# BIXS-V1_5.net
KiCad netlist of a schematic drawn in EAGLE
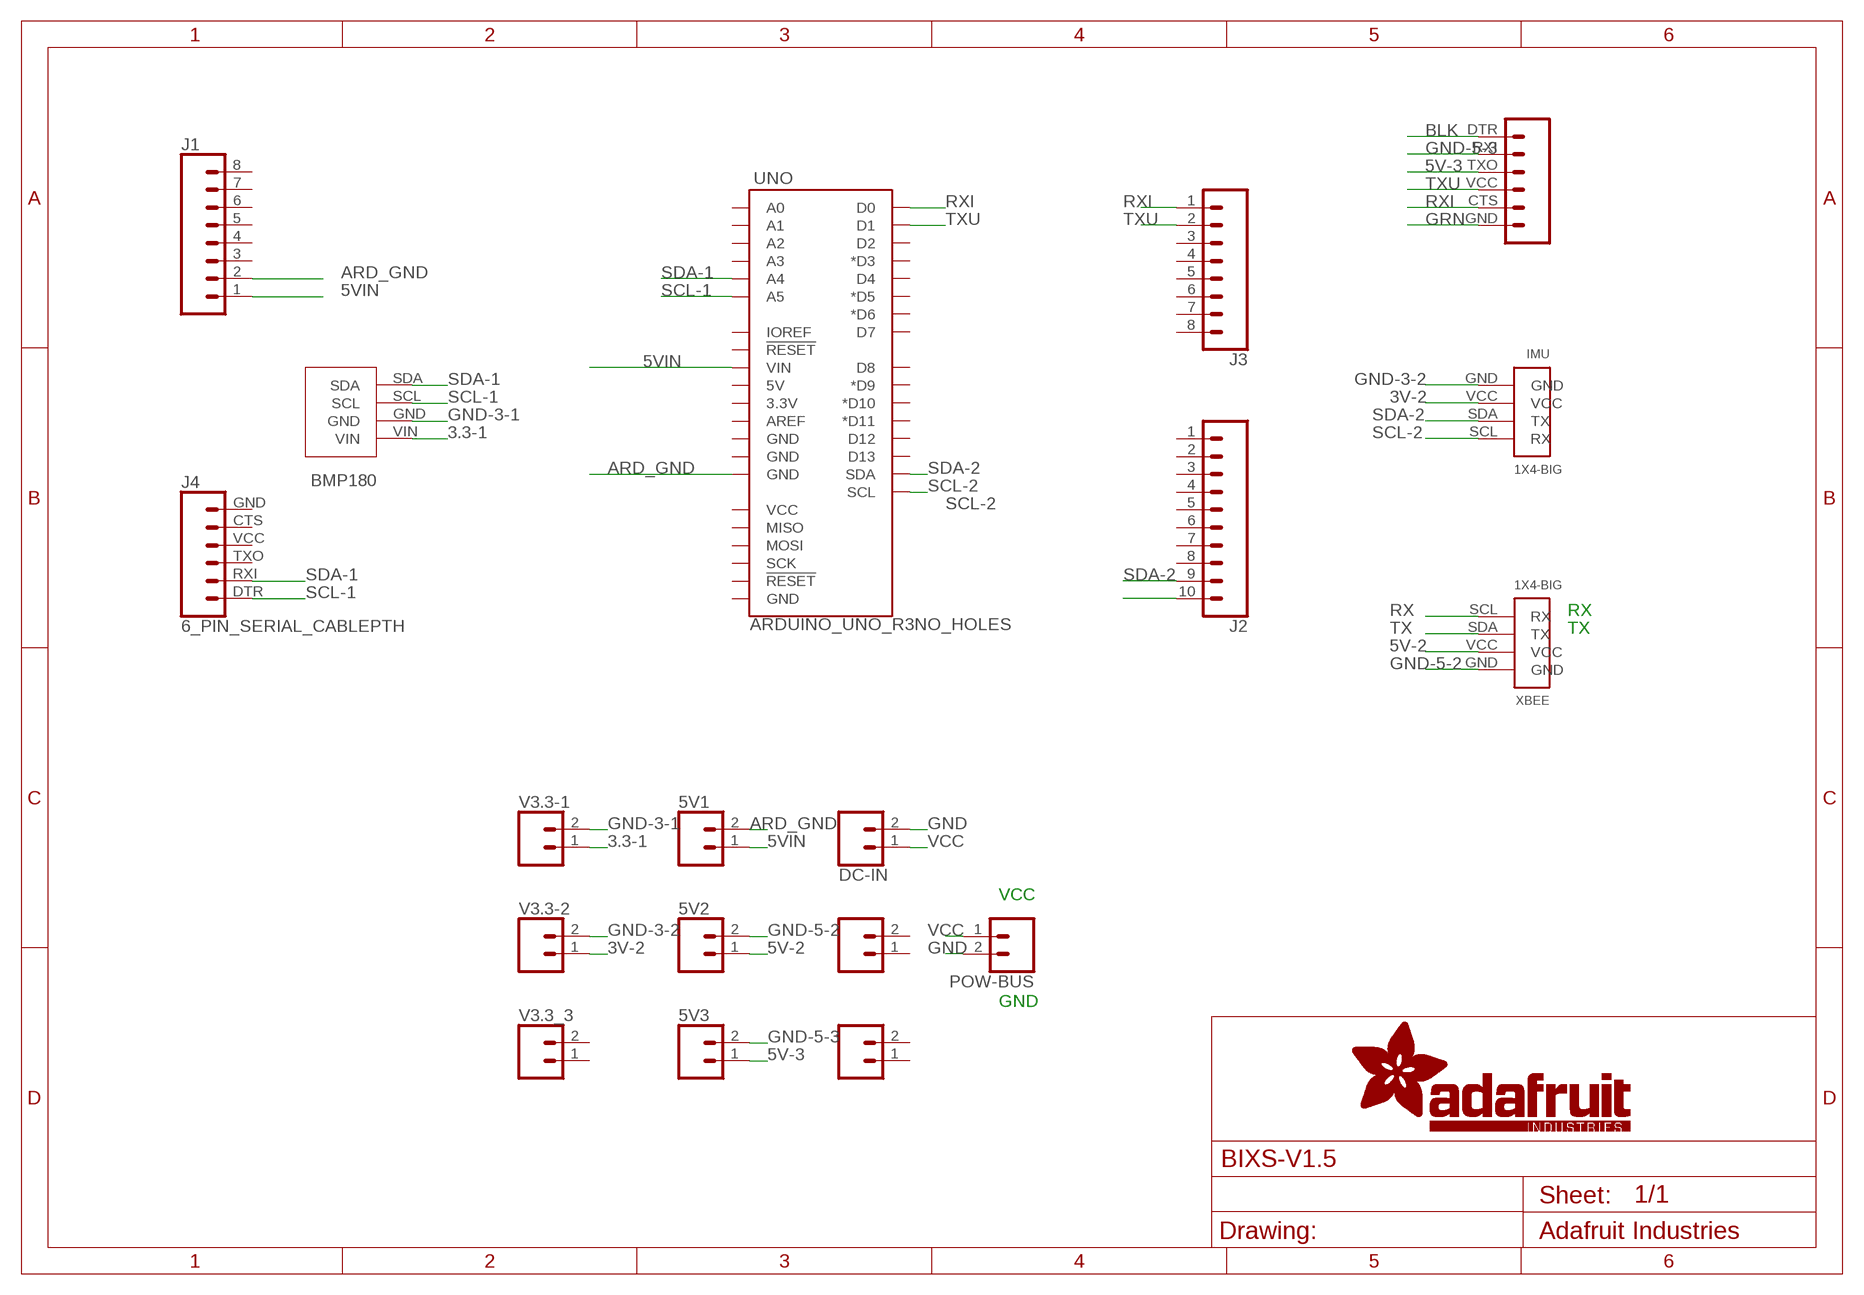
[diagram p0: schematic, sheet 1]

(export (version "E")
  (design (tool "Eeschema 10.0.6"))
  (components
    (comp (ref "5V1")
      (value "CONN_02")
      (footprint "eagle-import:1X02")
      (libsource (lib "eagle-import") (part "CONN_02"))
    )
    (comp (ref "5V2")
      (value "CONN_02")
      (footprint "eagle-import:1X02")
      (libsource (lib "eagle-import") (part "CONN_02"))
    )
    (comp (ref "5V3")
      (value "CONN_02")
      (footprint "eagle-import:1X02")
      (libsource (lib "eagle-import") (part "CONN_02"))
    )
    (comp (ref "BMP1")
      (value "BMP180")
      (footprint "eagle-import:BMP180")
      (libsource (lib "eagle-import") (part "BMP180"))
    )
    (comp (ref "DC_1")
      (value "CONN_02")
      (footprint "eagle-import:1X02")
      (libsource (lib "eagle-import") (part "CONN_02"))
    )
    (comp (ref "DC_2")
      (value "CONN_02")
      (footprint "eagle-import:1X02")
      (libsource (lib "eagle-import") (part "CONN_02"))
    )
    (comp (ref "DC_IN")
      (value "DC-IN")
      (footprint "eagle-import:1X02")
      (libsource (lib "eagle-import") (part "CONN_02"))
    )
    (comp (ref "IMU")
      (value "1X4-BIG")
      (footprint "eagle-import:1X04-BIG")
      (libsource (lib "eagle-import") (part "1X4-BIG"))
    )
    (comp (ref "J1")
      (value "CONN_08\"")
      (footprint "eagle-import:1X08")
      (libsource (lib "eagle-import") (part "CONN_08{dblquote}"))
    )
    (comp (ref "J2")
      (value "CONN_10\"")
      (footprint "eagle-import:1X10")
      (libsource (lib "eagle-import") (part "CONN_10{dblquote}"))
    )
    (comp (ref "J3")
      (value "CONN_08\"")
      (footprint "eagle-import:1X08")
      (libsource (lib "eagle-import") (part "CONN_08{dblquote}"))
    )
    (comp (ref "J4")
      (value "6_PIN_SERIAL_CABLEPTH")
      (footprint "eagle-import:FTDI_BASIC")
      (libsource (lib "eagle-import") (part "6_PIN_SERIAL_CABLEPTH"))
    )
    (comp (ref "MSD")
      (value "6_PIN_SERIAL_CABLEPTH")
      (footprint "eagle-import:FTDI_BASIC")
      (libsource (lib "eagle-import") (part "6_PIN_SERIAL_CABLEPTH"))
    )
    (comp (ref "POW-BUS")
      (value "CONN_02")
      (footprint "eagle-import:1X02")
      (libsource (lib "eagle-import") (part "CONN_02"))
    )
    (comp (ref "UNO")
      (value "ARDUINO_UNO_R3NO_HOLES")
      (footprint "eagle-import:ARDUINO_R3_NO_HOLES")
      (libsource (lib "eagle-import") (part "ARDUINO_UNO_R3NO_HOLES"))
    )
    (comp (ref "V3.3-1")
      (value "CONN_02")
      (footprint "eagle-import:1X02")
      (libsource (lib "eagle-import") (part "CONN_02"))
    )
    (comp (ref "V3.3-2")
      (value "CONN_02")
      (footprint "eagle-import:1X02")
      (libsource (lib "eagle-import") (part "CONN_02"))
    )
    (comp (ref "V3.3_3")
      (value "CONN_02")
      (footprint "eagle-import:1X02")
      (libsource (lib "eagle-import") (part "CONN_02"))
    )
    (comp (ref "XBEE")
      (value "1X4-BIG")
      (footprint "eagle-import:1X04-BIG")
      (libsource (lib "eagle-import") (part "1X4-BIG"))
    )
  )
  (nets
    (net (code "1") (name "/3.3-1") (class "Default")
      (node (ref "BMP1") (pin "VIN") (pinfunction "VIN_VIN") (pintype "bidirectional"))
      (node (ref "V3.3-1") (pin "1") (pinfunction "1_1") (pintype "passive"))
    )
    (net (code "2") (name "/3V-2") (class "Default")
      (node (ref "IMU") (pin "VCC") (pinfunction "VCC_VCC") (pintype "bidirectional"))
      (node (ref "V3.3-2") (pin "1") (pinfunction "1_1") (pintype "passive"))
    )
    (net (code "3") (name "/5V-2") (class "Default")
      (node (ref "5V2") (pin "1") (pinfunction "1_1") (pintype "passive"))
      (node (ref "XBEE") (pin "VCC") (pinfunction "VCC_VCC") (pintype "bidirectional"))
    )
    (net (code "4") (name "/5V-3") (class "Default")
      (node (ref "5V3") (pin "1") (pinfunction "1_1") (pintype "passive"))
      (node (ref "MSD") (pin "TXO") (pinfunction "VCC_TXO") (pintype "passive"))
    )
    (net (code "5") (name "/5VIN") (class "Default")
      (node (ref "5V1") (pin "1") (pinfunction "1_1") (pintype "passive"))
      (node (ref "J1") (pin "1") (pinfunction "1_1") (pintype "passive"))
      (node (ref "UNO") (pin "VIN") (pinfunction "VIN_VIN") (pintype "bidirectional"))
    )
    (net (code "6") (name "/ARD_GND") (class "Default")
      (node (ref "5V1") (pin "2") (pinfunction "2_2") (pintype "passive"))
      (node (ref "J1") (pin "2") (pinfunction "2_2") (pintype "passive"))
      (node (ref "UNO") (pin "GND@2") (pinfunction "GND_GND@2") (pintype "bidirectional"))
    )
    (net (code "7") (name "/BLK") (class "Default")
      (node (ref "MSD") (pin "DTR") (pinfunction "BLK_DTR") (pintype "passive"))
    )
    (net (code "8") (name "/GND") (class "Default")
      (node (ref "DC_IN") (pin "2") (pinfunction "2_2") (pintype "passive"))
      (node (ref "POW-BUS") (pin "2") (pinfunction "2_2") (pintype "passive"))
    )
    (net (code "9") (name "/GND-3-1") (class "Default")
      (node (ref "BMP1") (pin "GND") (pinfunction "GND_GND") (pintype "bidirectional"))
      (node (ref "V3.3-1") (pin "2") (pinfunction "2_2") (pintype "passive"))
    )
    (net (code "10") (name "/GND-3-2") (class "Default")
      (node (ref "IMU") (pin "GND") (pinfunction "GND_GND") (pintype "bidirectional"))
      (node (ref "V3.3-2") (pin "2") (pinfunction "2_2") (pintype "passive"))
    )
    (net (code "11") (name "/GND-5-2") (class "Default")
      (node (ref "5V2") (pin "2") (pinfunction "2_2") (pintype "passive"))
      (node (ref "XBEE") (pin "GND") (pinfunction "GND_GND") (pintype "bidirectional"))
    )
    (net (code "12") (name "/GND-5-3") (class "Default")
      (node (ref "5V3") (pin "2") (pinfunction "2_2") (pintype "passive"))
      (node (ref "MSD") (pin "RXI") (pinfunction "GND_RXI") (pintype "passive"))
    )
    (net (code "13") (name "/GRN") (class "Default")
      (node (ref "MSD") (pin "GND") (pinfunction "GRN_GND") (pintype "passive"))
    )
    (net (code "14") (name "/RX") (class "Default")
      (node (ref "XBEE") (pin "SCL") (pinfunction "RX_SCL") (pintype "bidirectional"))
    )
    (net (code "15") (name "/RXI") (class "Default")
      (node (ref "J3") (pin "1") (pinfunction "1_1") (pintype "passive"))
      (node (ref "MSD") (pin "CTS") (pinfunction "RXI_CTS") (pintype "passive"))
      (node (ref "UNO") (pin "D0") (pinfunction "D0_D0") (pintype "bidirectional"))
    )
    (net (code "16") (name "/SCL-1") (class "Default")
      (node (ref "BMP1") (pin "SCL") (pinfunction "SCL_SCL") (pintype "bidirectional"))
      (node (ref "J4") (pin "DTR") (pinfunction "BLK_DTR") (pintype "passive"))
      (node (ref "UNO") (pin "A5") (pinfunction "A5_A5") (pintype "bidirectional"))
    )
    (net (code "17") (name "/SCL-2") (class "Default")
      (node (ref "IMU") (pin "SCL") (pinfunction "RX_SCL") (pintype "bidirectional"))
      (node (ref "J2") (pin "10") (pinfunction "10_10") (pintype "passive"))
      (node (ref "UNO") (pin "SCL") (pinfunction "SCL_SCL") (pintype "bidirectional"))
    )
    (net (code "18") (name "/SDA-1") (class "Default")
      (node (ref "BMP1") (pin "SDA") (pinfunction "SDA_SDA") (pintype "bidirectional"))
      (node (ref "J4") (pin "RXI") (pinfunction "GND_RXI") (pintype "passive"))
      (node (ref "UNO") (pin "A4") (pinfunction "A4_A4") (pintype "bidirectional"))
    )
    (net (code "19") (name "/SDA-2") (class "Default")
      (node (ref "IMU") (pin "SDA") (pinfunction "TX_SDA") (pintype "bidirectional"))
      (node (ref "J2") (pin "9") (pinfunction "9_9") (pintype "passive"))
      (node (ref "UNO") (pin "SDA") (pinfunction "SDA_SDA") (pintype "bidirectional"))
    )
    (net (code "20") (name "/TX") (class "Default")
      (node (ref "XBEE") (pin "SDA") (pinfunction "TX_SDA") (pintype "bidirectional"))
    )
    (net (code "21") (name "/TXU") (class "Default")
      (node (ref "J3") (pin "2") (pinfunction "2_2") (pintype "passive"))
      (node (ref "MSD") (pin "VCC") (pinfunction "TXU_VCC") (pintype "passive"))
      (node (ref "UNO") (pin "D1") (pinfunction "D1_D1") (pintype "bidirectional"))
    )
    (net (code "22") (name "/VCC") (class "Default")
      (node (ref "DC_IN") (pin "1") (pinfunction "1_1") (pintype "passive"))
      (node (ref "POW-BUS") (pin "1") (pinfunction "1_1") (pintype "passive"))
    )
    (net (code "23") (name "unconnected-(DC_1-Pad1)") (class "Default")
      (node (ref "DC_1") (pin "1") (pinfunction "1_1") (pintype "passive"))
    )
    (net (code "24") (name "unconnected-(DC_1-Pad2)") (class "Default")
      (node (ref "DC_1") (pin "2") (pinfunction "2_2") (pintype "passive"))
    )
    (net (code "25") (name "unconnected-(DC_2-Pad1)") (class "Default")
      (node (ref "DC_2") (pin "1") (pinfunction "1_1") (pintype "passive"))
    )
    (net (code "26") (name "unconnected-(DC_2-Pad2)") (class "Default")
      (node (ref "DC_2") (pin "2") (pinfunction "2_2") (pintype "passive"))
    )
    (net (code "27") (name "unconnected-(J1-Pad3)") (class "Default")
      (node (ref "J1") (pin "3") (pinfunction "3_3") (pintype "passive"))
    )
    (net (code "28") (name "unconnected-(J1-Pad4)") (class "Default")
      (node (ref "J1") (pin "4") (pinfunction "4_4") (pintype "passive"))
    )
    (net (code "29") (name "unconnected-(J1-Pad5)") (class "Default")
      (node (ref "J1") (pin "5") (pinfunction "5_5") (pintype "passive"))
    )
    (net (code "30") (name "unconnected-(J1-Pad6)") (class "Default")
      (node (ref "J1") (pin "6") (pinfunction "6_6") (pintype "passive"))
    )
    (net (code "31") (name "unconnected-(J1-Pad7)") (class "Default")
      (node (ref "J1") (pin "7") (pinfunction "7_7") (pintype "passive"))
    )
    (net (code "32") (name "unconnected-(J1-Pad8)") (class "Default")
      (node (ref "J1") (pin "8") (pinfunction "8_8") (pintype "passive"))
    )
    (net (code "33") (name "unconnected-(J2-Pad1)") (class "Default")
      (node (ref "J2") (pin "1") (pinfunction "1_1") (pintype "passive"))
    )
    (net (code "34") (name "unconnected-(J2-Pad2)") (class "Default")
      (node (ref "J2") (pin "2") (pinfunction "2_2") (pintype "passive"))
    )
    (net (code "35") (name "unconnected-(J2-Pad3)") (class "Default")
      (node (ref "J2") (pin "3") (pinfunction "3_3") (pintype "passive"))
    )
    (net (code "36") (name "unconnected-(J2-Pad4)") (class "Default")
      (node (ref "J2") (pin "4") (pinfunction "4_4") (pintype "passive"))
    )
    (net (code "37") (name "unconnected-(J2-Pad5)") (class "Default")
      (node (ref "J2") (pin "5") (pinfunction "5_5") (pintype "passive"))
    )
    (net (code "38") (name "unconnected-(J2-Pad6)") (class "Default")
      (node (ref "J2") (pin "6") (pinfunction "6_6") (pintype "passive"))
    )
    (net (code "39") (name "unconnected-(J2-Pad7)") (class "Default")
      (node (ref "J2") (pin "7") (pinfunction "7_7") (pintype "passive"))
    )
    (net (code "40") (name "unconnected-(J2-Pad8)") (class "Default")
      (node (ref "J2") (pin "8") (pinfunction "8_8") (pintype "passive"))
    )
    (net (code "41") (name "unconnected-(J3-Pad3)") (class "Default")
      (node (ref "J3") (pin "3") (pinfunction "3_3") (pintype "passive"))
    )
    (net (code "42") (name "unconnected-(J3-Pad4)") (class "Default")
      (node (ref "J3") (pin "4") (pinfunction "4_4") (pintype "passive"))
    )
    (net (code "43") (name "unconnected-(J3-Pad5)") (class "Default")
      (node (ref "J3") (pin "5") (pinfunction "5_5") (pintype "passive"))
    )
    (net (code "44") (name "unconnected-(J3-Pad6)") (class "Default")
      (node (ref "J3") (pin "6") (pinfunction "6_6") (pintype "passive"))
    )
    (net (code "45") (name "unconnected-(J3-Pad7)") (class "Default")
      (node (ref "J3") (pin "7") (pinfunction "7_7") (pintype "passive"))
    )
    (net (code "46") (name "unconnected-(J3-Pad8)") (class "Default")
      (node (ref "J3") (pin "8") (pinfunction "8_8") (pintype "passive"))
    )
    (net (code "47") (name "unconnected-(J4-GRN-PadGND)") (class "Default")
      (node (ref "J4") (pin "GND") (pinfunction "GRN_GND") (pintype "passive"))
    )
    (net (code "48") (name "unconnected-(J4-RXI-PadCTS)") (class "Default")
      (node (ref "J4") (pin "CTS") (pinfunction "RXI_CTS") (pintype "passive"))
    )
    (net (code "49") (name "unconnected-(J4-TXU-PadVCC)") (class "Default")
      (node (ref "J4") (pin "VCC") (pinfunction "TXU_VCC") (pintype "passive"))
    )
    (net (code "50") (name "unconnected-(J4-VCC-PadTXO)") (class "Default")
      (node (ref "J4") (pin "TXO") (pinfunction "VCC_TXO") (pintype "passive"))
    )
    (net (code "51") (name "unconnected-(UNO-*D3-PadD3)") (class "Default")
      (node (ref "UNO") (pin "D3") (pinfunction "*D3_D3") (pintype "bidirectional"))
    )
    (net (code "52") (name "unconnected-(UNO-*D5-PadD5)") (class "Default")
      (node (ref "UNO") (pin "D5") (pinfunction "*D5_D5") (pintype "bidirectional"))
    )
    (net (code "53") (name "unconnected-(UNO-*D6-PadD6)") (class "Default")
      (node (ref "UNO") (pin "D6") (pinfunction "*D6_D6") (pintype "bidirectional"))
    )
    (net (code "54") (name "unconnected-(UNO-*D9-PadD9)") (class "Default")
      (node (ref "UNO") (pin "D9") (pinfunction "*D9_D9") (pintype "bidirectional"))
    )
    (net (code "55") (name "unconnected-(UNO-*D10-PadD10)") (class "Default")
      (node (ref "UNO") (pin "D10") (pinfunction "*D10_D10") (pintype "bidirectional"))
    )
    (net (code "56") (name "unconnected-(UNO-*D11-PadD11)") (class "Default")
      (node (ref "UNO") (pin "D11") (pinfunction "*D11_D11") (pintype "bidirectional"))
    )
    (net (code "57") (name "unconnected-(UNO-GND-PadGND@1)") (class "Default")
      (node (ref "UNO") (pin "GND@1") (pinfunction "GND_GND@1") (pintype "bidirectional"))
    )
    (net (code "58") (name "unconnected-(UNO-GND-PadGND@3)") (class "Default")
      (node (ref "UNO") (pin "GND@3") (pinfunction "GND_GND@3") (pintype "bidirectional"))
    )
    (net (code "59") (name "unconnected-(UNO-GND-PadGND@4)") (class "Default")
      (node (ref "UNO") (pin "GND@4") (pinfunction "GND_GND@4") (pintype "bidirectional"))
    )
    (net (code "60") (name "unconnected-(UNO-Pad3.3V)") (class "Default")
      (node (ref "UNO") (pin "3.3V") (pinfunction "3.3V_3.3V") (pintype "bidirectional"))
    )
    (net (code "61") (name "unconnected-(UNO-Pad5V)") (class "Default")
      (node (ref "UNO") (pin "5V") (pinfunction "5V_5V") (pintype "bidirectional"))
    )
    (net (code "62") (name "unconnected-(UNO-PadA0)") (class "Default")
      (node (ref "UNO") (pin "A0") (pinfunction "A0_A0") (pintype "bidirectional"))
    )
    (net (code "63") (name "unconnected-(UNO-PadA1)") (class "Default")
      (node (ref "UNO") (pin "A1") (pinfunction "A1_A1") (pintype "bidirectional"))
    )
    (net (code "64") (name "unconnected-(UNO-PadA2)") (class "Default")
      (node (ref "UNO") (pin "A2") (pinfunction "A2_A2") (pintype "bidirectional"))
    )
    (net (code "65") (name "unconnected-(UNO-PadA3)") (class "Default")
      (node (ref "UNO") (pin "A3") (pinfunction "A3_A3") (pintype "bidirectional"))
    )
    (net (code "66") (name "unconnected-(UNO-PadAREF)") (class "Default")
      (node (ref "UNO") (pin "AREF") (pinfunction "AREF_AREF") (pintype "bidirectional"))
    )
    (net (code "67") (name "unconnected-(UNO-PadD2)") (class "Default")
      (node (ref "UNO") (pin "D2") (pinfunction "D2_D2") (pintype "bidirectional"))
    )
    (net (code "68") (name "unconnected-(UNO-PadD4)") (class "Default")
      (node (ref "UNO") (pin "D4") (pinfunction "D4_D4") (pintype "bidirectional"))
    )
    (net (code "69") (name "unconnected-(UNO-PadD7)") (class "Default")
      (node (ref "UNO") (pin "D7") (pinfunction "D7_D7") (pintype "bidirectional"))
    )
    (net (code "70") (name "unconnected-(UNO-PadD8)") (class "Default")
      (node (ref "UNO") (pin "D8") (pinfunction "D8_D8") (pintype "bidirectional"))
    )
    (net (code "71") (name "unconnected-(UNO-PadD12)") (class "Default")
      (node (ref "UNO") (pin "D12") (pinfunction "D12_D12") (pintype "bidirectional"))
    )
    (net (code "72") (name "unconnected-(UNO-PadD13)") (class "Default")
      (node (ref "UNO") (pin "D13") (pinfunction "D13_D13") (pintype "bidirectional"))
    )
    (net (code "73") (name "unconnected-(UNO-PadIOREF)") (class "Default")
      (node (ref "UNO") (pin "IOREF") (pinfunction "IOREF_IOREF") (pintype "bidirectional"))
    )
    (net (code "74") (name "unconnected-(UNO-PadMISO)") (class "Default")
      (node (ref "UNO") (pin "MISO") (pinfunction "MISO_MISO") (pintype "bidirectional"))
    )
    (net (code "75") (name "unconnected-(UNO-PadMOSI)") (class "Default")
      (node (ref "UNO") (pin "MOSI") (pinfunction "MOSI_MOSI") (pintype "bidirectional"))
    )
    (net (code "76") (name "unconnected-(UNO-PadSCK)") (class "Default")
      (node (ref "UNO") (pin "SCK") (pinfunction "SCK_SCK") (pintype "bidirectional"))
    )
    (net (code "77") (name "unconnected-(UNO-PadVCC)") (class "Default")
      (node (ref "UNO") (pin "VCC") (pinfunction "VCC_VCC") (pintype "bidirectional"))
    )
    (net (code "78") (name "unconnected-(UNO-~{RESET}-PadRESET@1)") (class "Default")
      (node (ref "UNO") (pin "RESET@1") (pinfunction "~{RESET}_RESET@1") (pintype "bidirectional"))
    )
    (net (code "79") (name "unconnected-(UNO-~{RESET}-PadRESET@2)") (class "Default")
      (node (ref "UNO") (pin "RESET@2") (pinfunction "~{RESET}_RESET@2") (pintype "bidirectional"))
    )
    (net (code "80") (name "unconnected-(V3.3_3-Pad1)") (class "Default")
      (node (ref "V3.3_3") (pin "1") (pinfunction "1_1") (pintype "passive"))
    )
    (net (code "81") (name "unconnected-(V3.3_3-Pad2)") (class "Default")
      (node (ref "V3.3_3") (pin "2") (pinfunction "2_2") (pintype "passive"))
    )
  )
)
